# schematic.net
KiCad netlist of a schematic drawn in EAGLE
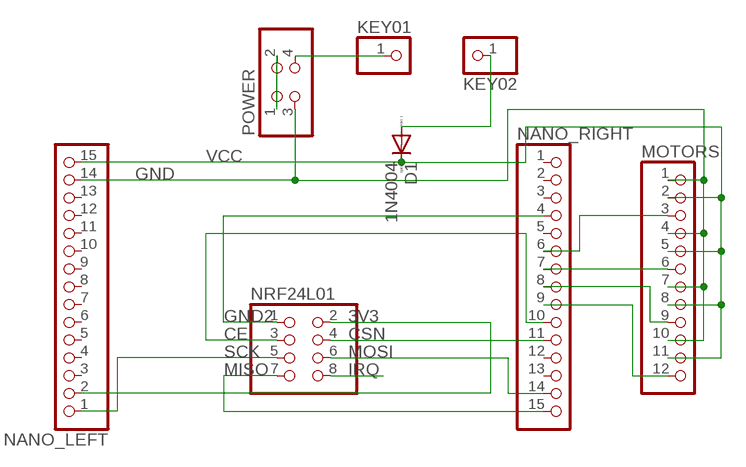
[diagram p0: schematic, sheet 1]

(export (version "E")
  (design (tool "Eeschema 10.0.6"))
  (components
    (comp (ref "D1")
      (value "1N4004")
      (footprint "eagle-import:DO41-10")
      (libsource (lib "eagle-import") (part "1N4004"))
    )
    (comp (ref "KEY01")
      (value "PINHD-1X1")
      (footprint "eagle-import:1X01")
      (libsource (lib "eagle-import") (part "PINHD-1X1"))
    )
    (comp (ref "KEY02")
      (value "PINHD-1X1")
      (footprint "eagle-import:1X01")
      (libsource (lib "eagle-import") (part "PINHD-1X1"))
    )
    (comp (ref "MOTORS")
      (value "PINHD-1X12")
      (footprint "eagle-import:1X12")
      (libsource (lib "eagle-import") (part "PINHD-1X12"))
    )
    (comp (ref "NANO_LEFT")
      (value "PINHD-1X15")
      (footprint "eagle-import:1X15")
      (libsource (lib "eagle-import") (part "PINHD-1X15"))
    )
    (comp (ref "NANO_RIGHT")
      (value "PINHD-1X15")
      (footprint "eagle-import:1X15")
      (libsource (lib "eagle-import") (part "PINHD-1X15"))
    )
    (comp (ref "NRF24L01")
      (value "PINHD-2X4")
      (footprint "eagle-import:2X04")
      (libsource (lib "eagle-import") (part "PINHD-2X4"))
    )
    (comp (ref "POWER")
      (value "PINHD-2X2")
      (footprint "eagle-import:2X02")
      (libsource (lib "eagle-import") (part "PINHD-2X2"))
    )
  )
  (nets
    (net (code "1") (name "/3V3") (class "Default")
      (node (ref "NANO_LEFT") (pin "2") (pinfunction "2_2") (pintype "passive"))
      (node (ref "NRF24L01") (pin "2") (pinfunction "2_2") (pintype "passive"))
    )
    (net (code "2") (name "/CE") (class "Default")
      (node (ref "NANO_RIGHT") (pin "10") (pinfunction "10_10") (pintype "passive"))
      (node (ref "NRF24L01") (pin "3") (pinfunction "3_3") (pintype "passive"))
    )
    (net (code "3") (name "/CSN") (class "Default")
      (node (ref "NANO_RIGHT") (pin "11") (pinfunction "11_11") (pintype "passive"))
      (node (ref "NRF24L01") (pin "4") (pinfunction "4_4") (pintype "passive"))
    )
    (net (code "4") (name "/GND") (class "Default")
      (node (ref "MOTORS") (pin "1") (pinfunction "1_1") (pintype "passive"))
      (node (ref "MOTORS") (pin "10") (pinfunction "10_10") (pintype "passive"))
      (node (ref "MOTORS") (pin "4") (pinfunction "4_4") (pintype "passive"))
      (node (ref "MOTORS") (pin "7") (pinfunction "7_7") (pintype "passive"))
      (node (ref "NANO_LEFT") (pin "14") (pinfunction "14_14") (pintype "passive"))
      (node (ref "POWER") (pin "3") (pinfunction "3_3") (pintype "passive"))
    )
    (net (code "5") (name "/GND2") (class "Default")
      (node (ref "NANO_RIGHT") (pin "4") (pinfunction "4_4") (pintype "passive"))
      (node (ref "NRF24L01") (pin "1") (pinfunction "1_1") (pintype "passive"))
    )
    (net (code "6") (name "/IRQ") (class "Default")
      (node (ref "NRF24L01") (pin "8") (pinfunction "8_8") (pintype "passive"))
    )
    (net (code "7") (name "/MISO") (class "Default")
      (node (ref "NANO_RIGHT") (pin "15") (pinfunction "15_15") (pintype "passive"))
      (node (ref "NRF24L01") (pin "7") (pinfunction "7_7") (pintype "passive"))
    )
    (net (code "8") (name "/MOSI") (class "Default")
      (node (ref "NANO_RIGHT") (pin "14") (pinfunction "14_14") (pintype "passive"))
      (node (ref "NRF24L01") (pin "6") (pinfunction "6_6") (pintype "passive"))
    )
    (net (code "9") (name "/SCK") (class "Default")
      (node (ref "NANO_LEFT") (pin "1") (pinfunction "1_1") (pintype "passive"))
      (node (ref "NRF24L01") (pin "5") (pinfunction "5_5") (pintype "passive"))
    )
    (net (code "10") (name "/VCC") (class "Default")
      (node (ref "D1") (pin "C") (pinfunction "C_C") (pintype "passive"))
      (node (ref "MOTORS") (pin "11") (pinfunction "11_11") (pintype "passive"))
      (node (ref "MOTORS") (pin "2") (pinfunction "2_2") (pintype "passive"))
      (node (ref "MOTORS") (pin "5") (pinfunction "5_5") (pintype "passive"))
      (node (ref "MOTORS") (pin "8") (pinfunction "8_8") (pintype "passive"))
      (node (ref "NANO_LEFT") (pin "15") (pinfunction "15_15") (pintype "passive"))
    )
    (net (code "11") (name "Net-(D1-PadA)") (class "Default")
      (node (ref "D1") (pin "A") (pinfunction "A_A") (pintype "passive"))
      (node (ref "KEY02") (pin "1") (pinfunction "1_1") (pintype "passive"))
    )
    (net (code "12") (name "Net-(KEY01-Pad1)") (class "Default")
      (node (ref "KEY01") (pin "1") (pinfunction "1_1") (pintype "passive"))
      (node (ref "POWER") (pin "4") (pinfunction "4_4") (pintype "passive"))
    )
    (net (code "13") (name "Net-(MOTORS-Pad3)") (class "Default")
      (node (ref "MOTORS") (pin "3") (pinfunction "3_3") (pintype "passive"))
      (node (ref "NANO_RIGHT") (pin "6") (pinfunction "6_6") (pintype "passive"))
    )
    (net (code "14") (name "Net-(MOTORS-Pad6)") (class "Default")
      (node (ref "MOTORS") (pin "6") (pinfunction "6_6") (pintype "passive"))
      (node (ref "NANO_RIGHT") (pin "7") (pinfunction "7_7") (pintype "passive"))
    )
    (net (code "15") (name "Net-(MOTORS-Pad9)") (class "Default")
      (node (ref "MOTORS") (pin "9") (pinfunction "9_9") (pintype "passive"))
      (node (ref "NANO_RIGHT") (pin "8") (pinfunction "8_8") (pintype "passive"))
    )
    (net (code "16") (name "Net-(MOTORS-Pad12)") (class "Default")
      (node (ref "MOTORS") (pin "12") (pinfunction "12_12") (pintype "passive"))
      (node (ref "NANO_RIGHT") (pin "9") (pinfunction "9_9") (pintype "passive"))
    )
    (net (code "17") (name "Net-(POWER-Pad1)") (class "Default")
      (node (ref "POWER") (pin "1") (pinfunction "1_1") (pintype "passive"))
      (node (ref "POWER") (pin "2") (pinfunction "2_2") (pintype "passive"))
    )
    (net (code "18") (name "unconnected-(NANO_LEFT-Pad3)") (class "Default")
      (node (ref "NANO_LEFT") (pin "3") (pinfunction "3_3") (pintype "passive"))
    )
    (net (code "19") (name "unconnected-(NANO_LEFT-Pad4)") (class "Default")
      (node (ref "NANO_LEFT") (pin "4") (pinfunction "4_4") (pintype "passive"))
    )
    (net (code "20") (name "unconnected-(NANO_LEFT-Pad5)") (class "Default")
      (node (ref "NANO_LEFT") (pin "5") (pinfunction "5_5") (pintype "passive"))
    )
    (net (code "21") (name "unconnected-(NANO_LEFT-Pad6)") (class "Default")
      (node (ref "NANO_LEFT") (pin "6") (pinfunction "6_6") (pintype "passive"))
    )
    (net (code "22") (name "unconnected-(NANO_LEFT-Pad7)") (class "Default")
      (node (ref "NANO_LEFT") (pin "7") (pinfunction "7_7") (pintype "passive"))
    )
    (net (code "23") (name "unconnected-(NANO_LEFT-Pad8)") (class "Default")
      (node (ref "NANO_LEFT") (pin "8") (pinfunction "8_8") (pintype "passive"))
    )
    (net (code "24") (name "unconnected-(NANO_LEFT-Pad9)") (class "Default")
      (node (ref "NANO_LEFT") (pin "9") (pinfunction "9_9") (pintype "passive"))
    )
    (net (code "25") (name "unconnected-(NANO_LEFT-Pad10)") (class "Default")
      (node (ref "NANO_LEFT") (pin "10") (pinfunction "10_10") (pintype "passive"))
    )
    (net (code "26") (name "unconnected-(NANO_LEFT-Pad11)") (class "Default")
      (node (ref "NANO_LEFT") (pin "11") (pinfunction "11_11") (pintype "passive"))
    )
    (net (code "27") (name "unconnected-(NANO_LEFT-Pad12)") (class "Default")
      (node (ref "NANO_LEFT") (pin "12") (pinfunction "12_12") (pintype "passive"))
    )
    (net (code "28") (name "unconnected-(NANO_LEFT-Pad13)") (class "Default")
      (node (ref "NANO_LEFT") (pin "13") (pinfunction "13_13") (pintype "passive"))
    )
    (net (code "29") (name "unconnected-(NANO_RIGHT-Pad1)") (class "Default")
      (node (ref "NANO_RIGHT") (pin "1") (pinfunction "1_1") (pintype "passive"))
    )
    (net (code "30") (name "unconnected-(NANO_RIGHT-Pad2)") (class "Default")
      (node (ref "NANO_RIGHT") (pin "2") (pinfunction "2_2") (pintype "passive"))
    )
    (net (code "31") (name "unconnected-(NANO_RIGHT-Pad3)") (class "Default")
      (node (ref "NANO_RIGHT") (pin "3") (pinfunction "3_3") (pintype "passive"))
    )
    (net (code "32") (name "unconnected-(NANO_RIGHT-Pad5)") (class "Default")
      (node (ref "NANO_RIGHT") (pin "5") (pinfunction "5_5") (pintype "passive"))
    )
    (net (code "33") (name "unconnected-(NANO_RIGHT-Pad12)") (class "Default")
      (node (ref "NANO_RIGHT") (pin "12") (pinfunction "12_12") (pintype "passive"))
    )
    (net (code "34") (name "unconnected-(NANO_RIGHT-Pad13)") (class "Default")
      (node (ref "NANO_RIGHT") (pin "13") (pinfunction "13_13") (pintype "passive"))
    )
  )
)
